# QRP_SSB_20m.net
KiCad netlist of a schematic drawn in EAGLE
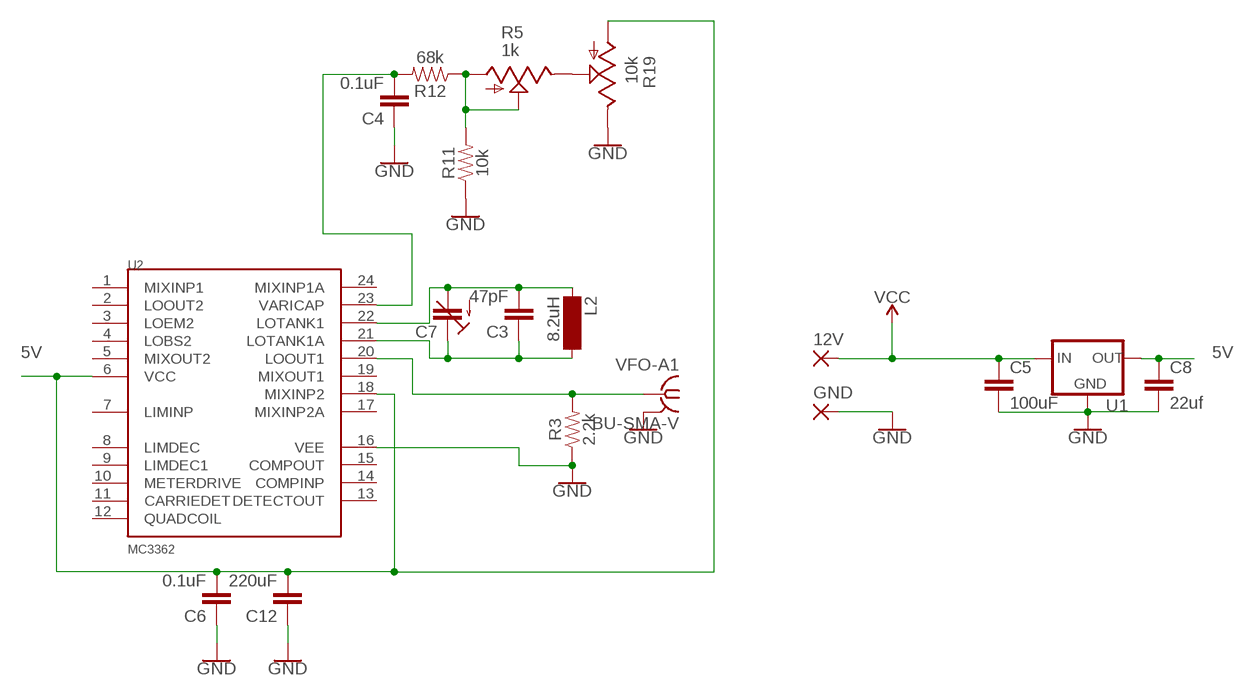
[diagram p0: schematic, sheet 1]

(export (version "E")
  (design (tool "Eeschema 10.0.6"))
  (components
    (comp (ref "12V")
      (value "3,17/1,1")
      (footprint "eagle-import:3,17_1,1")
      (libsource (lib "eagle-import") (part "3,17/1,1"))
    )
    (comp (ref "C3")
      (value "47pF")
      (footprint "eagle-import:C5B3.5")
      (libsource (lib "eagle-import") (part "C5/3.5"))
    )
    (comp (ref "C4")
      (value "0.1uF")
      (footprint "eagle-import:C5B3.5")
      (libsource (lib "eagle-import") (part "C5/3.5"))
    )
    (comp (ref "C5")
      (value "100uF")
      (footprint "eagle-import:C5B3.5")
      (libsource (lib "eagle-import") (part "C5/3.5"))
    )
    (comp (ref "C6")
      (value "0.1uF")
      (footprint "eagle-import:C5B3.5")
      (libsource (lib "eagle-import") (part "C5/3.5"))
    )
    (comp (ref "C7")
      (value "C-TRIMMTZ03")
      (footprint "eagle-import:CTRIMTZ03")
      (libsource (lib "eagle-import") (part "C-TRIMMTZ03"))
    )
    (comp (ref "C8")
      (value "22uf")
      (footprint "eagle-import:C5B3.5")
      (libsource (lib "eagle-import") (part "C5/3.5"))
    )
    (comp (ref "C12")
      (value "220uF")
      (footprint "eagle-import:C5B3.5")
      (libsource (lib "eagle-import") (part "C5/3.5"))
    )
    (comp (ref "GND")
      (value "3,17/1,1")
      (footprint "eagle-import:3,17_1,1")
      (libsource (lib "eagle-import") (part "3,17/1,1"))
    )
    (comp (ref "L2")
      (value "8.2uH")
      (footprint "eagle-import:BS75")
      (libsource (lib "eagle-import") (part "BS75"))
    )
    (comp (ref "R3")
      (value "2.2k")
      (footprint "eagle-import:AXIAL-0.3")
      (libsource (lib "eagle-import") (part "1KOHM-HORIZ-1/4W-1%"))
    )
    (comp (ref "R5")
      (value "1k")
      (footprint "eagle-import:B25V")
      (libsource (lib "eagle-import") (part "TRIM_US-B25V"))
    )
    (comp (ref "R11")
      (value "10k")
      (footprint "eagle-import:AXIAL-0.3")
      (libsource (lib "eagle-import") (part "1KOHM-HORIZ-1/4W-1%"))
    )
    (comp (ref "R12")
      (value "68k")
      (footprint "eagle-import:AXIAL-0.3")
      (libsource (lib "eagle-import") (part "1KOHM-HORIZ-1/4W-1%"))
    )
    (comp (ref "R19")
      (value "10k")
      (footprint "eagle-import:B25V")
      (libsource (lib "eagle-import") (part "TRIM_US-B25V"))
    )
    (comp (ref "U1")
      (value "V_REG_78XXTO-92_UNTESTED")
      (footprint "eagle-import:TO-92")
      (libsource (lib "eagle-import") (part "V_REG_78XXTO-92_UNTESTED"))
    )
    (comp (ref "U2")
      (value "MC3362")
      (footprint "eagle-import:DIP24")
      (libsource (lib "eagle-import") (part "MC3362"))
    )
    (comp (ref "VFO-A1")
      (value "BU-SMA-V")
      (footprint "eagle-import:BU-SMA-V")
      (libsource (lib "eagle-import") (part "BU-SMA-V"))
    )
  )
  (nets
    (net (code "1") (name "/5V") (class "Default")
      (node (ref "C12") (pin "2") (pinfunction "2_2") (pintype "passive"))
      (node (ref "C6") (pin "2") (pinfunction "2_2") (pintype "passive"))
      (node (ref "C8") (pin "1") (pinfunction "1_1") (pintype "passive"))
      (node (ref "R19") (pin "A") (pinfunction "A_A") (pintype "passive"))
      (node (ref "U1") (pin "1") (pinfunction "OUT_1") (pintype "passive"))
      (node (ref "U2") (pin "18") (pinfunction "MIXINP2_18") (pintype "bidirectional"))
      (node (ref "U2") (pin "6") (pinfunction "VCC_6") (pintype "bidirectional"))
    )
    (net (code "2") (name "GND") (class "Default")
      (node (ref "C12") (pin "1") (pinfunction "1_1") (pintype "passive"))
      (node (ref "C4") (pin "1") (pinfunction "1_1") (pintype "passive"))
      (node (ref "C5") (pin "2") (pinfunction "2_2") (pintype "passive"))
      (node (ref "C6") (pin "1") (pinfunction "1_1") (pintype "passive"))
      (node (ref "C8") (pin "2") (pinfunction "2_2") (pintype "passive"))
      (node (ref "GND") (pin "1") (pinfunction "P_1") (pintype "passive"))
      (node (ref "R11") (pin "P$1") (pinfunction "1_P$1") (pintype "passive"))
      (node (ref "R19") (pin "E") (pinfunction "E_E") (pintype "passive"))
      (node (ref "R3") (pin "P$1") (pinfunction "1_P$1") (pintype "passive"))
      (node (ref "U1") (pin "2") (pinfunction "GND_2") (pintype "input"))
      (node (ref "U2") (pin "16") (pinfunction "VEE_16") (pintype "bidirectional"))
      (node (ref "VFO-A1") (pin "2") (pinfunction "2_2") (pintype "passive"))
      (node (ref "VFO-A1") (pin "3") (pinfunction "2_3") (pintype "passive"))
      (node (ref "VFO-A1") (pin "4") (pinfunction "2_4") (pintype "passive"))
      (node (ref "VFO-A1") (pin "5") (pinfunction "2_5") (pintype "passive"))
    )
    (net (code "3") (name "Net-(C7-A)") (class "Default")
      (node (ref "C3") (pin "2") (pinfunction "2_2") (pintype "passive"))
      (node (ref "C7") (pin "2") (pinfunction "A_2") (pintype "passive"))
      (node (ref "L2") (pin "1") (pinfunction "1_1") (pintype "passive"))
      (node (ref "U2") (pin "22") (pinfunction "LOTANK1_22") (pintype "bidirectional"))
    )
    (net (code "4") (name "Net-(C7-E)") (class "Default")
      (node (ref "C3") (pin "1") (pinfunction "1_1") (pintype "passive"))
      (node (ref "C7") (pin "1") (pinfunction "E_1") (pintype "passive"))
      (node (ref "L2") (pin "2") (pinfunction "2_2") (pintype "passive"))
      (node (ref "U2") (pin "21") (pinfunction "LOTANK1A_21") (pintype "bidirectional"))
    )
    (net (code "5") (name "Net-(R3-2)") (class "Default")
      (node (ref "R3") (pin "P$2") (pinfunction "2_P$2") (pintype "passive"))
      (node (ref "U2") (pin "20") (pinfunction "LOOUT1_20") (pintype "bidirectional"))
      (node (ref "VFO-A1") (pin "1") (pinfunction "1_1") (pintype "passive"))
    )
    (net (code "6") (name "Net-(R11-2)") (class "Default")
      (node (ref "R11") (pin "P$2") (pinfunction "2_P$2") (pintype "passive"))
      (node (ref "R12") (pin "P$1") (pinfunction "1_P$1") (pintype "passive"))
      (node (ref "R5") (pin "A") (pinfunction "A_A") (pintype "passive"))
      (node (ref "R5") (pin "S") (pinfunction "S_S") (pintype "passive"))
    )
    (net (code "7") (name "Net-(R12-2)") (class "Default")
      (node (ref "C4") (pin "2") (pinfunction "2_2") (pintype "passive"))
      (node (ref "R12") (pin "P$2") (pinfunction "2_P$2") (pintype "passive"))
      (node (ref "U2") (pin "23") (pinfunction "VARICAP_23") (pintype "bidirectional"))
    )
    (net (code "8") (name "Net-(R19-PadS)") (class "Default")
      (node (ref "R19") (pin "S") (pinfunction "S_S") (pintype "passive"))
      (node (ref "R5") (pin "E") (pinfunction "E_E") (pintype "passive"))
    )
    (net (code "9") (name "VCC") (class "Default")
      (node (ref "12V") (pin "1") (pinfunction "P_1") (pintype "passive"))
      (node (ref "C5") (pin "1") (pinfunction "1_1") (pintype "passive"))
      (node (ref "U1") (pin "3") (pinfunction "IN_3") (pintype "input"))
    )
    (net (code "10") (name "unconnected-(U2-CARRIEDET-Pad11)") (class "Default")
      (node (ref "U2") (pin "11") (pinfunction "CARRIEDET_11") (pintype "bidirectional"))
    )
    (net (code "11") (name "unconnected-(U2-COMPINP-Pad14)") (class "Default")
      (node (ref "U2") (pin "14") (pinfunction "COMPINP_14") (pintype "bidirectional"))
    )
    (net (code "12") (name "unconnected-(U2-COMPOUT-Pad15)") (class "Default")
      (node (ref "U2") (pin "15") (pinfunction "COMPOUT_15") (pintype "bidirectional"))
    )
    (net (code "13") (name "unconnected-(U2-DETECTOUT-Pad13)") (class "Default")
      (node (ref "U2") (pin "13") (pinfunction "DETECTOUT_13") (pintype "bidirectional"))
    )
    (net (code "14") (name "unconnected-(U2-LIMDEC-Pad8)") (class "Default")
      (node (ref "U2") (pin "8") (pinfunction "LIMDEC_8") (pintype "bidirectional"))
    )
    (net (code "15") (name "unconnected-(U2-LIMDEC1-Pad9)") (class "Default")
      (node (ref "U2") (pin "9") (pinfunction "LIMDEC1_9") (pintype "bidirectional"))
    )
    (net (code "16") (name "unconnected-(U2-LIMINP-Pad7)") (class "Default")
      (node (ref "U2") (pin "7") (pinfunction "LIMINP_7") (pintype "bidirectional"))
    )
    (net (code "17") (name "unconnected-(U2-LOBS2-Pad4)") (class "Default")
      (node (ref "U2") (pin "4") (pinfunction "LOBS2_4") (pintype "bidirectional"))
    )
    (net (code "18") (name "unconnected-(U2-LOEM2-Pad3)") (class "Default")
      (node (ref "U2") (pin "3") (pinfunction "LOEM2_3") (pintype "bidirectional"))
    )
    (net (code "19") (name "unconnected-(U2-LOOUT2-Pad2)") (class "Default")
      (node (ref "U2") (pin "2") (pinfunction "LOOUT2_2") (pintype "bidirectional"))
    )
    (net (code "20") (name "unconnected-(U2-METERDRIVE-Pad10)") (class "Default")
      (node (ref "U2") (pin "10") (pinfunction "METERDRIVE_10") (pintype "bidirectional"))
    )
    (net (code "21") (name "unconnected-(U2-MIXINP1-Pad1)") (class "Default")
      (node (ref "U2") (pin "1") (pinfunction "MIXINP1_1") (pintype "bidirectional"))
    )
    (net (code "22") (name "unconnected-(U2-MIXINP1A-Pad24)") (class "Default")
      (node (ref "U2") (pin "24") (pinfunction "MIXINP1A_24") (pintype "bidirectional"))
    )
    (net (code "23") (name "unconnected-(U2-MIXINP2A-Pad17)") (class "Default")
      (node (ref "U2") (pin "17") (pinfunction "MIXINP2A_17") (pintype "bidirectional"))
    )
    (net (code "24") (name "unconnected-(U2-MIXOUT1-Pad19)") (class "Default")
      (node (ref "U2") (pin "19") (pinfunction "MIXOUT1_19") (pintype "bidirectional"))
    )
    (net (code "25") (name "unconnected-(U2-MIXOUT2-Pad5)") (class "Default")
      (node (ref "U2") (pin "5") (pinfunction "MIXOUT2_5") (pintype "bidirectional"))
    )
    (net (code "26") (name "unconnected-(U2-QUADCOIL-Pad12)") (class "Default")
      (node (ref "U2") (pin "12") (pinfunction "QUADCOIL_12") (pintype "bidirectional"))
    )
  )
)
